# MCU_Main.net
KiCad netlist of a schematic drawn in Altium Designer
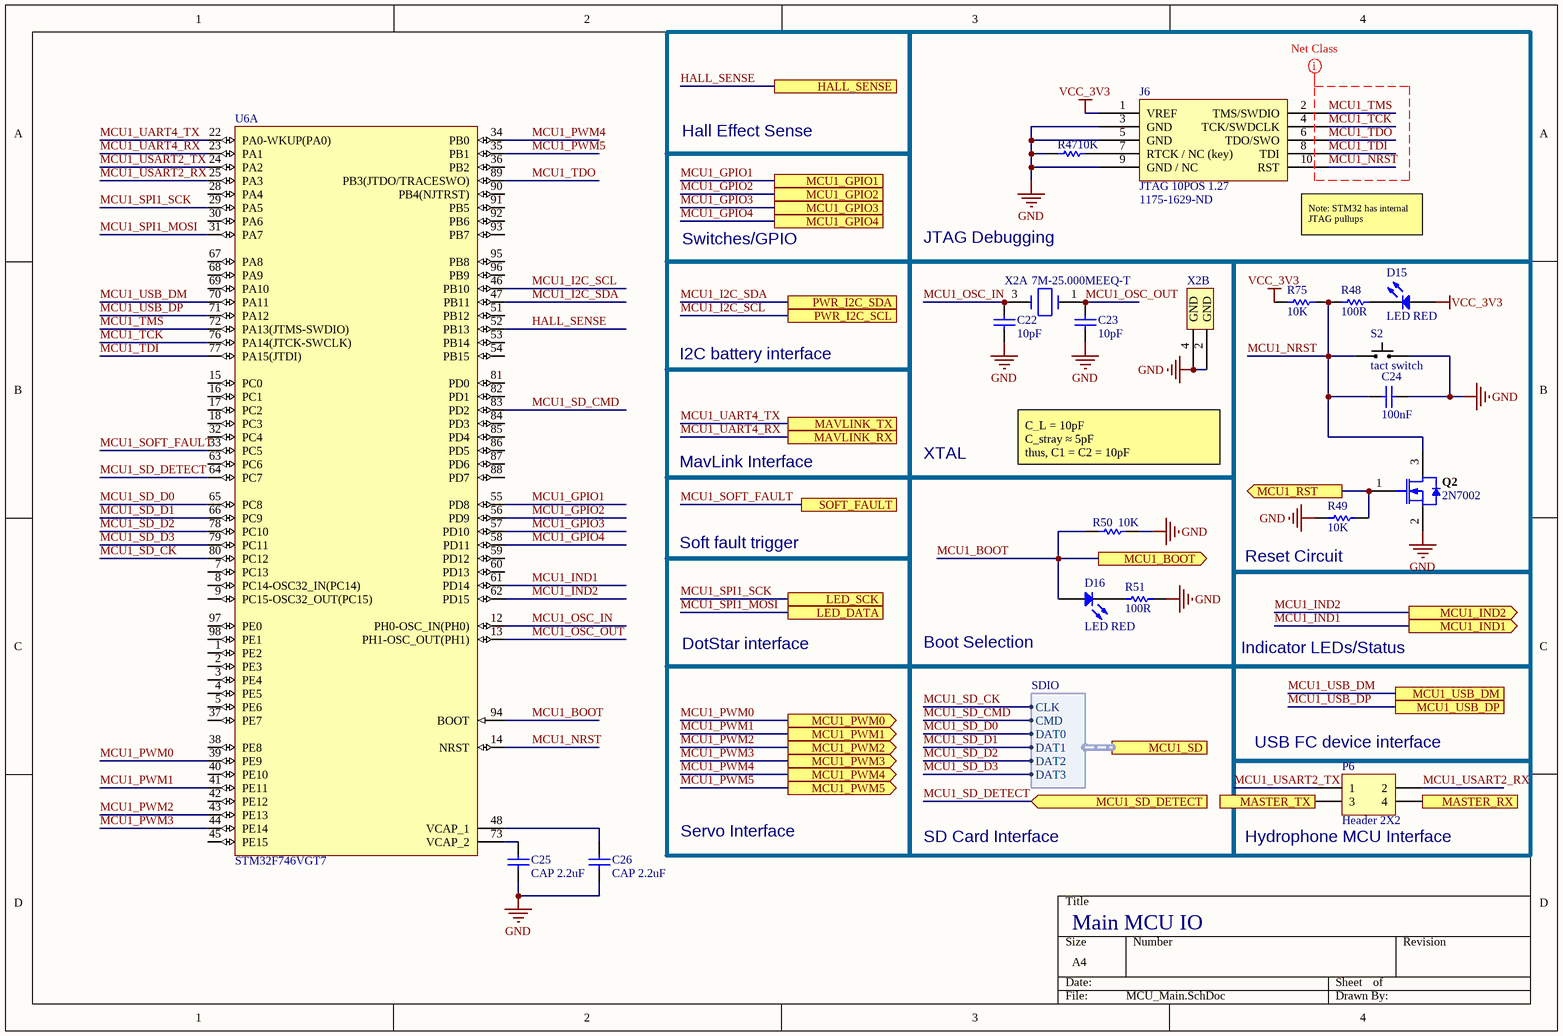
[diagram p0: MCU_Main.SchDoc]

(export (version "E")
  (design (tool "Eeschema 10.0.6"))
  (components
    (comp (ref "C22")
      (value "10pF")
      (footprint "CAPC0603(1608)100_N")
      (description "CAP 10pF 25V ±1% 0603 (1608 Metric) Thickness 1mm SMD")
      (fields (field (name "TOLERANCE") "Â±1%"))
      (libsource (lib "Altium Content Vault") (part "CAP"))
    )
    (comp (ref "C23")
      (value "10pF")
      (footprint "CAPC0603(1608)100_N")
      (description "CAP 10pF 25V ±1% 0603 (1608 Metric) Thickness 1mm SMD")
      (fields (field (name "TOLERANCE") "Â±1%"))
      (libsource (lib "Altium Content Vault") (part "CAP"))
    )
    (comp (ref "C24")
      (value "100nF")
      (footprint "CAPC0603(1608)100_N")
      (description "CAP 100nF 10V ±10% 0603 (1608 Metric) Thickness 1mm SMD")
      (fields (field (name "TOLERANCE") "Â±10%"))
      (libsource (lib "Altium Content Vault") (part "CAP"))
    )
    (comp (ref "C25")
      (value "CAP 2.2uF")
      (footprint "CAPC0603(1608)100_N")
      (description "CAP 2.2uF 10V ±10% 0603 (1608 Metric) Thickness 1mm SMD")
      (fields (field (name "TOLERANCE") "Â±10%"))
      (libsource (lib "Altium Content Vault") (part "CAP"))
    )
    (comp (ref "C26")
      (value "CAP 2.2uF")
      (footprint "CAPC0603(1608)100_N")
      (description "CAP 2.2uF 10V ±10% 0603 (1608 Metric) Thickness 1mm SMD")
      (fields (field (name "TOLERANCE") "Â±10%"))
      (libsource (lib "Altium Content Vault") (part "CAP"))
    )
    (comp (ref "D15")
      (value "LED RED")
      (footprint "LED_0805")
      (description "led")
      (fields
        (field (name "MANUFACTURER") "Lite-On Inc.")
        (field (name "MANUFACTURER PART NUMBER") "LTST-C171KRKT")
      )
      (libsource (lib "CMR_Miscellaneous_Devices") (part "LED0"))
    )
    (comp (ref "D16")
      (value "LED RED")
      (footprint "LED_0805")
      (description "led")
      (fields
        (field (name "MANUFACTURER") "Lite-On Inc.")
        (field (name "MANUFACTURER PART NUMBER") "LTST-C171KRKT")
      )
      (libsource (lib "CMR_Miscellaneous_Devices") (part "LED0"))
    )
    (comp (ref "J6")
      (value "JTAG 10POS 1.27")
      (footprint "5x2 JTAG SMD")
      (fields (field (name "SUPPLIER PART NUMBER 1") "1175-1629-ND"))
      (libsource (lib "CMR_Miscellaneous_Devices") (part "jtag 10pos mini"))
    )
    (comp (ref "P6")
      (value "Header 2X2")
      (footprint "HDR2X2")
      (description "Header, 2-Pin, Dual row")
      (fields (field (name "PUBLISHER") "Altium Limited"))
      (libsource (lib "Miscellaneous Connectors") (part "Header 2X2"))
    )
    (comp (ref "Q2")
      (value "2N7002")
      (footprint "INF-PG-SOT23_M")
      (fields (field (name "MANUFACTURER") "Infineon"))
      (libsource (lib "Altium Content Vault") (part "INF-NDMOS-GSD-3"))
    )
    (comp (ref "R47")
      (value "10K")
      (footprint "RESC0603(1608)_N")
      (description "10K 0.1W 5% 0603 (1608 Metric)  SMD")
      (fields (field (name "TOLERANCE") "5 %") (field (name "POWER") "0.1 W"))
      (libsource (lib "Altium Content Vault") (part "RES"))
    )
    (comp (ref "R48")
      (value "100R")
      (footprint "RESC0603(1608)_N")
      (description "100R 0.1W 5% 0603 (1608 Metric)  SMD")
      (fields (field (name "TOLERANCE") "5 %") (field (name "POWER") "0.1 W"))
      (libsource (lib "Altium Content Vault") (part "RES"))
    )
    (comp (ref "R49")
      (value "10K")
      (footprint "RESC0603(1608)_N")
      (description "10K 0.1W 5% 0603 (1608 Metric)  SMD")
      (fields (field (name "TOLERANCE") "5 %") (field (name "POWER") "0.1 W"))
      (libsource (lib "Altium Content Vault") (part "RES"))
    )
    (comp (ref "R50")
      (value "10K")
      (footprint "RESC0603(1608)_N")
      (description "10K 0.1W 5% 0603 (1608 Metric)  SMD")
      (fields (field (name "TOLERANCE") "5 %") (field (name "POWER") "0.1 W"))
      (libsource (lib "Altium Content Vault") (part "RES"))
    )
    (comp (ref "R51")
      (value "100R")
      (footprint "RESC0603(1608)_N")
      (description "100R 0.1W 5% 0603 (1608 Metric)  SMD")
      (fields (field (name "TOLERANCE") "5 %") (field (name "POWER") "0.1 W"))
      (libsource (lib "Altium Content Vault") (part "RES"))
    )
    (comp (ref "R75")
      (value "10K")
      (footprint "RESC0603(1608)_N")
      (description "10K 0.1W 5% 0603 (1608 Metric)  SMD")
      (fields (field (name "TOLERANCE") "5 %") (field (name "POWER") "0.1 W"))
      (libsource (lib "Altium Content Vault") (part "RES"))
    )
    (comp (ref "S2")
      (value "tact switch")
      (footprint "EVP-AA202K")
      (description "EVP-AA Momentary Switch SPST-NO")
      (fields (field (name "PART NUMBER") "EVP-AA202K"))
      (libsource (lib "CMR_Miscellaneous_Devices") (part "EVP-AA Switch"))
    )
    (comp (ref "U6")
      (value "STM32F746VGT7")
      (footprint "STM-LQFP100_L")
      (libsource (lib "Altium Content Vault") (part "MC-ARM-STM32F7X6-LQFP100"))
    )
    (comp (ref "X2")
      (value "7M-25.000MEEQ-T")
      (footprint "OSCSC320X250X100N")
      (description "CRYSTAL 25.0000MHZ 10PF SMD")
      (fields (field (name "TOLERANCE") "10ppm"))
      (libsource (lib "") (part "7M-25.000MEEQ-T_1"))
    )
  )
  (nets
    (net (code "2") (name "/HALL_SENSE") (class "Default")
      (node (ref "U6") (pin "52") (pinfunction "PB13_52") (pintype "bidirectional"))
    )
    (net (code "3") (name "/MASTER_RX") (class "Default")
      (node (ref "P6") (pin "4") (pinfunction "4_4") (pintype "passive"))
    )
    (net (code "4") (name "/MASTER_TX") (class "Default")
      (node (ref "P6") (pin "3") (pinfunction "3_3") (pintype "passive"))
    )
    (net (code "5") (name "/MCU1_BOOT") (class "Default")
      (node (ref "D16") (pin "2") (pinfunction "A_2") (pintype "passive"))
      (node (ref "R50") (pin "1") (pinfunction "1_1") (pintype "passive"))
      (node (ref "U6") (pin "94") (pinfunction "BOOT_94") (pintype "input"))
    )
    (net (code "6") (name "/MCU1_GPIO1") (class "Default")
      (node (ref "U6") (pin "55") (pinfunction "PD8_55") (pintype "bidirectional"))
    )
    (net (code "7") (name "/MCU1_GPIO2") (class "Default")
      (node (ref "U6") (pin "56") (pinfunction "PD9_56") (pintype "bidirectional"))
    )
    (net (code "8") (name "/MCU1_GPIO3") (class "Default")
      (node (ref "U6") (pin "57") (pinfunction "PD10_57") (pintype "bidirectional"))
    )
    (net (code "9") (name "/MCU1_GPIO4") (class "Default")
      (node (ref "U6") (pin "58") (pinfunction "PD11_58") (pintype "bidirectional"))
    )
    (net (code "10") (name "/MCU1_I2C_SCL") (class "Default")
      (node (ref "U6") (pin "46") (pinfunction "PB10_46") (pintype "bidirectional"))
    )
    (net (code "11") (name "/MCU1_I2C_SDA") (class "Default")
      (node (ref "U6") (pin "47") (pinfunction "PB11_47") (pintype "bidirectional"))
    )
    (net (code "12") (name "/MCU1_IND1") (class "Default")
      (node (ref "U6") (pin "61") (pinfunction "PD14_61") (pintype "bidirectional"))
    )
    (net (code "13") (name "/MCU1_IND2") (class "Default")
      (node (ref "U6") (pin "62") (pinfunction "PD15_62") (pintype "bidirectional"))
    )
    (net (code "14") (name "/MCU1_NRST") (class "Default")
      (node (ref "C24") (pin "2") (pinfunction "2_2") (pintype "passive"))
      (node (ref "J6") (pin "10") (pinfunction "RST_10") (pintype "passive"))
      (node (ref "Q2") (pin "3") (pinfunction "DRAIN_3") (pintype "passive"))
      (node (ref "R48") (pin "2") (pinfunction "2_2") (pintype "passive"))
      (node (ref "R75") (pin "1") (pinfunction "1_1") (pintype "passive"))
      (node (ref "S2") (pin "1") (pinfunction "1_1") (pintype "passive"))
      (node (ref "U6") (pin "14") (pinfunction "NRST_14") (pintype "bidirectional"))
    )
    (net (code "15") (name "/MCU1_OSC_IN") (class "Default")
      (node (ref "C22") (pin "2") (pinfunction "2_2") (pintype "passive"))
      (node (ref "U6") (pin "12") (pinfunction "PH0-OSC_IN(PH0)_12") (pintype "bidirectional"))
      (node (ref "X2") (pin "3") (pintype "passive"))
    )
    (net (code "16") (name "/MCU1_OSC_OUT") (class "Default")
      (node (ref "C23") (pin "2") (pinfunction "2_2") (pintype "passive"))
      (node (ref "U6") (pin "13") (pinfunction "PH1-OSC_OUT(PH1)_13") (pintype "bidirectional"))
      (node (ref "X2") (pin "1") (pinfunction "11_1") (pintype "passive"))
    )
    (net (code "17") (name "/MCU1_PWM0") (class "Default")
      (node (ref "U6") (pin "39") (pinfunction "PE9_39") (pintype "bidirectional"))
    )
    (net (code "18") (name "/MCU1_PWM1") (class "Default")
      (node (ref "U6") (pin "41") (pinfunction "PE11_41") (pintype "bidirectional"))
    )
    (net (code "19") (name "/MCU1_PWM2") (class "Default")
      (node (ref "U6") (pin "43") (pinfunction "PE13_43") (pintype "bidirectional"))
    )
    (net (code "20") (name "/MCU1_PWM3") (class "Default")
      (node (ref "U6") (pin "44") (pinfunction "PE14_44") (pintype "bidirectional"))
    )
    (net (code "21") (name "/MCU1_PWM4") (class "Default")
      (node (ref "U6") (pin "34") (pinfunction "PB0_34") (pintype "bidirectional"))
    )
    (net (code "22") (name "/MCU1_PWM5") (class "Default")
      (node (ref "U6") (pin "35") (pinfunction "PB1_35") (pintype "bidirectional"))
    )
    (net (code "23") (name "/MCU1_RST") (class "Default")
      (node (ref "Q2") (pin "1") (pinfunction "GATE_1") (pintype "passive"))
      (node (ref "R49") (pin "1") (pinfunction "1_1") (pintype "passive"))
    )
    (net (code "24") (name "/MCU1_SD_CK") (class "Default")
      (node (ref "U6") (pin "80") (pinfunction "PC12_80") (pintype "bidirectional"))
    )
    (net (code "25") (name "/MCU1_SD_CMD") (class "Default")
      (node (ref "U6") (pin "83") (pinfunction "PD2_83") (pintype "bidirectional"))
    )
    (net (code "26") (name "/MCU1_SD_D0") (class "Default")
      (node (ref "U6") (pin "65") (pinfunction "PC8_65") (pintype "bidirectional"))
    )
    (net (code "27") (name "/MCU1_SD_D1") (class "Default")
      (node (ref "U6") (pin "66") (pinfunction "PC9_66") (pintype "bidirectional"))
    )
    (net (code "28") (name "/MCU1_SD_D2") (class "Default")
      (node (ref "U6") (pin "78") (pinfunction "PC10_78") (pintype "bidirectional"))
    )
    (net (code "29") (name "/MCU1_SD_D3") (class "Default")
      (node (ref "U6") (pin "79") (pinfunction "PC11_79") (pintype "bidirectional"))
    )
    (net (code "30") (name "/MCU1_SD_DETECT") (class "Default")
      (node (ref "U6") (pin "64") (pinfunction "PC7_64") (pintype "bidirectional"))
    )
    (net (code "31") (name "/MCU1_SOFT_FAULT") (class "Default")
      (node (ref "U6") (pin "33") (pinfunction "PC5_33") (pintype "bidirectional"))
    )
    (net (code "32") (name "/MCU1_SPI1_MOSI") (class "Default")
      (node (ref "U6") (pin "31") (pinfunction "PA7_31") (pintype "bidirectional"))
    )
    (net (code "33") (name "/MCU1_SPI1_SCK") (class "Default")
      (node (ref "U6") (pin "29") (pinfunction "PA5_29") (pintype "bidirectional"))
    )
    (net (code "34") (name "/MCU1_TCK") (class "Default")
      (node (ref "J6") (pin "4") (pinfunction "TCK/SWDCLK_4") (pintype "passive"))
      (node (ref "U6") (pin "76") (pinfunction "PA14(JTCK-SWCLK)_76") (pintype "bidirectional"))
    )
    (net (code "35") (name "/MCU1_TDI") (class "Default")
      (node (ref "J6") (pin "8") (pinfunction "TDI_8") (pintype "passive"))
      (node (ref "U6") (pin "77") (pinfunction "PA15(JTDI)_77") (pintype "bidirectional"))
    )
    (net (code "36") (name "/MCU1_TDO") (class "Default")
      (node (ref "J6") (pin "6") (pinfunction "TDO/SWO_6") (pintype "passive"))
      (node (ref "U6") (pin "89") (pinfunction "PB3(JTDO/TRACESWO)_89") (pintype "bidirectional"))
    )
    (net (code "37") (name "/MCU1_TMS") (class "Default")
      (node (ref "J6") (pin "2") (pinfunction "TMS/SWDIO_2") (pintype "passive"))
      (node (ref "U6") (pin "72") (pinfunction "PA13(JTMS-SWDIO)_72") (pintype "bidirectional"))
    )
    (net (code "38") (name "/MCU1_UART4_RX") (class "Default")
      (node (ref "U6") (pin "23") (pinfunction "PA1_23") (pintype "bidirectional"))
    )
    (net (code "39") (name "/MCU1_UART4_TX") (class "Default")
      (node (ref "U6") (pin "22") (pinfunction "PA0-WKUP(PA0)_22") (pintype "bidirectional"))
    )
    (net (code "40") (name "/MCU1_USART2_RX") (class "Default")
      (node (ref "P6") (pin "2") (pinfunction "2_2") (pintype "passive"))
      (node (ref "U6") (pin "25") (pinfunction "PA3_25") (pintype "bidirectional"))
    )
    (net (code "41") (name "/MCU1_USART2_TX") (class "Default")
      (node (ref "P6") (pin "1") (pinfunction "1_1") (pintype "passive"))
      (node (ref "U6") (pin "24") (pinfunction "PA2_24") (pintype "bidirectional"))
    )
    (net (code "42") (name "/MCU1_USB_DM") (class "Default")
      (node (ref "U6") (pin "70") (pinfunction "PA11_70") (pintype "bidirectional"))
    )
    (net (code "43") (name "/MCU1_USB_DP") (class "Default")
      (node (ref "U6") (pin "71") (pinfunction "PA12_71") (pintype "bidirectional"))
    )
    (net (code "45") (name "GND") (class "Default")
      (node (ref "C22") (pin "1") (pinfunction "1_1") (pintype "passive"))
      (node (ref "C23") (pin "1") (pinfunction "1_1") (pintype "passive"))
      (node (ref "C24") (pin "1") (pinfunction "1_1") (pintype "passive"))
      (node (ref "C25") (pin "1") (pinfunction "1_1") (pintype "passive"))
      (node (ref "C26") (pin "1") (pinfunction "1_1") (pintype "passive"))
      (node (ref "J6") (pin "3") (pinfunction "GND_3") (pintype "passive"))
      (node (ref "J6") (pin "5") (pinfunction "GND_5") (pintype "passive"))
      (node (ref "J6") (pin "9") (pinfunction "GND_/_NC_9") (pintype "passive"))
      (node (ref "Q2") (pin "2") (pinfunction "SOURCE_2") (pintype "passive"))
      (node (ref "R47") (pin "1") (pinfunction "1_1") (pintype "passive"))
      (node (ref "R49") (pin "2") (pinfunction "2_2") (pintype "passive"))
      (node (ref "R50") (pin "2") (pinfunction "2_2") (pintype "passive"))
      (node (ref "R51") (pin "2") (pinfunction "2_2") (pintype "passive"))
      (node (ref "S2") (pin "2") (pinfunction "2_2") (pintype "passive"))
      (node (ref "X2") (pin "2") (pinfunction "GND_2") (pintype "passive"))
      (node (ref "X2") (pin "4") (pinfunction "GND_4") (pintype "passive"))
    )
    (net (code "46") (name "Net-(D15-K)") (class "Default")
      (node (ref "D15") (pin "1") (pinfunction "K_1") (pintype "passive"))
      (node (ref "R48") (pin "1") (pinfunction "1_1") (pintype "passive"))
    )
    (net (code "47") (name "Net-(D16-K)") (class "Default")
      (node (ref "D16") (pin "1") (pinfunction "K_1") (pintype "passive"))
      (node (ref "R51") (pin "1") (pinfunction "1_1") (pintype "passive"))
    )
    (net (code "48") (name "Net-(J6-RTCK_{slash}_NC_(key))") (class "Default")
      (node (ref "J6") (pin "7") (pinfunction "RTCK_/_NC_(key)_7") (pintype "passive"))
      (node (ref "R47") (pin "2") (pinfunction "2_2") (pintype "passive"))
    )
    (net (code "49") (name "Net-(U6A-VCAP_1)") (class "Default")
      (node (ref "C26") (pin "2") (pinfunction "2_2") (pintype "passive"))
      (node (ref "U6") (pin "48") (pinfunction "VCAP_1_48") (pintype "passive"))
    )
    (net (code "50") (name "Net-(U6A-VCAP_2)") (class "Default")
      (node (ref "C25") (pin "2") (pinfunction "2_2") (pintype "passive"))
      (node (ref "U6") (pin "73") (pinfunction "VCAP_2_73") (pintype "passive"))
    )
    (net (code "51") (name "VCC_3V3") (class "Default")
      (node (ref "D15") (pin "2") (pinfunction "A_2") (pintype "passive"))
      (node (ref "J6") (pin "1") (pinfunction "VREF_1") (pintype "passive"))
      (node (ref "R75") (pin "2") (pinfunction "2_2") (pintype "passive"))
    )
    (net (code "52") (name "unconnected-(U6A-PA4-Pad28)") (class "Default")
      (node (ref "U6") (pin "28") (pinfunction "PA4_28") (pintype "bidirectional"))
    )
    (net (code "53") (name "unconnected-(U6A-PA6-Pad30)") (class "Default")
      (node (ref "U6") (pin "30") (pinfunction "PA6_30") (pintype "bidirectional"))
    )
    (net (code "54") (name "unconnected-(U6A-PA8-Pad67)") (class "Default")
      (node (ref "U6") (pin "67") (pinfunction "PA8_67") (pintype "bidirectional"))
    )
    (net (code "55") (name "unconnected-(U6A-PA9-Pad68)") (class "Default")
      (node (ref "U6") (pin "68") (pinfunction "PA9_68") (pintype "bidirectional"))
    )
    (net (code "56") (name "unconnected-(U6A-PA10-Pad69)") (class "Default")
      (node (ref "U6") (pin "69") (pinfunction "PA10_69") (pintype "bidirectional"))
    )
    (net (code "57") (name "unconnected-(U6A-PB2-Pad36)") (class "Default")
      (node (ref "U6") (pin "36") (pinfunction "PB2_36") (pintype "bidirectional"))
    )
    (net (code "58") (name "unconnected-(U6A-PB4(NJTRST)-Pad90)") (class "Default")
      (node (ref "U6") (pin "90") (pinfunction "PB4(NJTRST)_90") (pintype "bidirectional"))
    )
    (net (code "59") (name "unconnected-(U6A-PB5-Pad91)") (class "Default")
      (node (ref "U6") (pin "91") (pinfunction "PB5_91") (pintype "bidirectional"))
    )
    (net (code "60") (name "unconnected-(U6A-PB6-Pad92)") (class "Default")
      (node (ref "U6") (pin "92") (pinfunction "PB6_92") (pintype "bidirectional"))
    )
    (net (code "61") (name "unconnected-(U6A-PB7-Pad93)") (class "Default")
      (node (ref "U6") (pin "93") (pinfunction "PB7_93") (pintype "bidirectional"))
    )
    (net (code "62") (name "unconnected-(U6A-PB8-Pad95)") (class "Default")
      (node (ref "U6") (pin "95") (pinfunction "PB8_95") (pintype "bidirectional"))
    )
    (net (code "63") (name "unconnected-(U6A-PB9-Pad96)") (class "Default")
      (node (ref "U6") (pin "96") (pinfunction "PB9_96") (pintype "bidirectional"))
    )
    (net (code "64") (name "unconnected-(U6A-PB12-Pad51)") (class "Default")
      (node (ref "U6") (pin "51") (pinfunction "PB12_51") (pintype "bidirectional"))
    )
    (net (code "65") (name "unconnected-(U6A-PB14-Pad53)") (class "Default")
      (node (ref "U6") (pin "53") (pinfunction "PB14_53") (pintype "bidirectional"))
    )
    (net (code "66") (name "unconnected-(U6A-PB15-Pad54)") (class "Default")
      (node (ref "U6") (pin "54") (pinfunction "PB15_54") (pintype "bidirectional"))
    )
    (net (code "67") (name "unconnected-(U6A-PC0-Pad15)") (class "Default")
      (node (ref "U6") (pin "15") (pinfunction "PC0_15") (pintype "bidirectional"))
    )
    (net (code "68") (name "unconnected-(U6A-PC1-Pad16)") (class "Default")
      (node (ref "U6") (pin "16") (pinfunction "PC1_16") (pintype "bidirectional"))
    )
    (net (code "69") (name "unconnected-(U6A-PC2-Pad17)") (class "Default")
      (node (ref "U6") (pin "17") (pinfunction "PC2_17") (pintype "bidirectional"))
    )
    (net (code "70") (name "unconnected-(U6A-PC3-Pad18)") (class "Default")
      (node (ref "U6") (pin "18") (pinfunction "PC3_18") (pintype "bidirectional"))
    )
    (net (code "71") (name "unconnected-(U6A-PC4-Pad32)") (class "Default")
      (node (ref "U6") (pin "32") (pinfunction "PC4_32") (pintype "bidirectional"))
    )
    (net (code "72") (name "unconnected-(U6A-PC6-Pad63)") (class "Default")
      (node (ref "U6") (pin "63") (pinfunction "PC6_63") (pintype "bidirectional"))
    )
    (net (code "73") (name "unconnected-(U6A-PC13-Pad7)") (class "Default")
      (node (ref "U6") (pin "7") (pinfunction "PC13_7") (pintype "bidirectional"))
    )
    (net (code "74") (name "unconnected-(U6A-PC14-OSC32_IN(PC14)-Pad8)") (class "Default")
      (node (ref "U6") (pin "8") (pinfunction "PC14-OSC32_IN(PC14)_8") (pintype "bidirectional"))
    )
    (net (code "75") (name "unconnected-(U6A-PC15-OSC32_OUT(PC15)-Pad9)") (class "Default")
      (node (ref "U6") (pin "9") (pinfunction "PC15-OSC32_OUT(PC15)_9") (pintype "bidirectional"))
    )
    (net (code "76") (name "unconnected-(U6A-PD0-Pad81)") (class "Default")
      (node (ref "U6") (pin "81") (pinfunction "PD0_81") (pintype "bidirectional"))
    )
    (net (code "77") (name "unconnected-(U6A-PD1-Pad82)") (class "Default")
      (node (ref "U6") (pin "82") (pinfunction "PD1_82") (pintype "bidirectional"))
    )
    (net (code "78") (name "unconnected-(U6A-PD3-Pad84)") (class "Default")
      (node (ref "U6") (pin "84") (pinfunction "PD3_84") (pintype "bidirectional"))
    )
    (net (code "79") (name "unconnected-(U6A-PD4-Pad85)") (class "Default")
      (node (ref "U6") (pin "85") (pinfunction "PD4_85") (pintype "bidirectional"))
    )
    (net (code "80") (name "unconnected-(U6A-PD5-Pad86)") (class "Default")
      (node (ref "U6") (pin "86") (pinfunction "PD5_86") (pintype "bidirectional"))
    )
    (net (code "81") (name "unconnected-(U6A-PD6-Pad87)") (class "Default")
      (node (ref "U6") (pin "87") (pinfunction "PD6_87") (pintype "bidirectional"))
    )
    (net (code "82") (name "unconnected-(U6A-PD7-Pad88)") (class "Default")
      (node (ref "U6") (pin "88") (pinfunction "PD7_88") (pintype "bidirectional"))
    )
    (net (code "83") (name "unconnected-(U6A-PD12-Pad59)") (class "Default")
      (node (ref "U6") (pin "59") (pinfunction "PD12_59") (pintype "bidirectional"))
    )
    (net (code "84") (name "unconnected-(U6A-PD13-Pad60)") (class "Default")
      (node (ref "U6") (pin "60") (pinfunction "PD13_60") (pintype "bidirectional"))
    )
    (net (code "85") (name "unconnected-(U6A-PE0-Pad97)") (class "Default")
      (node (ref "U6") (pin "97") (pinfunction "PE0_97") (pintype "bidirectional"))
    )
    (net (code "86") (name "unconnected-(U6A-PE1-Pad98)") (class "Default")
      (node (ref "U6") (pin "98") (pinfunction "PE1_98") (pintype "bidirectional"))
    )
    (net (code "87") (name "unconnected-(U6A-PE2-Pad1)") (class "Default")
      (node (ref "U6") (pin "1") (pinfunction "PE2_1") (pintype "bidirectional"))
    )
    (net (code "88") (name "unconnected-(U6A-PE3-Pad2)") (class "Default")
      (node (ref "U6") (pin "2") (pinfunction "PE3_2") (pintype "bidirectional"))
    )
    (net (code "89") (name "unconnected-(U6A-PE4-Pad3)") (class "Default")
      (node (ref "U6") (pin "3") (pinfunction "PE4_3") (pintype "bidirectional"))
    )
    (net (code "90") (name "unconnected-(U6A-PE5-Pad4)") (class "Default")
      (node (ref "U6") (pin "4") (pinfunction "PE5_4") (pintype "bidirectional"))
    )
    (net (code "91") (name "unconnected-(U6A-PE6-Pad5)") (class "Default")
      (node (ref "U6") (pin "5") (pinfunction "PE6_5") (pintype "bidirectional"))
    )
    (net (code "92") (name "unconnected-(U6A-PE7-Pad37)") (class "Default")
      (node (ref "U6") (pin "37") (pinfunction "PE7_37") (pintype "bidirectional"))
    )
    (net (code "93") (name "unconnected-(U6A-PE8-Pad38)") (class "Default")
      (node (ref "U6") (pin "38") (pinfunction "PE8_38") (pintype "bidirectional"))
    )
    (net (code "94") (name "unconnected-(U6A-PE10-Pad40)") (class "Default")
      (node (ref "U6") (pin "40") (pinfunction "PE10_40") (pintype "bidirectional"))
    )
    (net (code "95") (name "unconnected-(U6A-PE12-Pad42)") (class "Default")
      (node (ref "U6") (pin "42") (pinfunction "PE12_42") (pintype "bidirectional"))
    )
    (net (code "96") (name "unconnected-(U6A-PE15-Pad45)") (class "Default")
      (node (ref "U6") (pin "45") (pinfunction "PE15_45") (pintype "bidirectional"))
    )
  )
)
